# Infinity_Camera.net
KiCad netlist of a schematic drawn in EAGLE
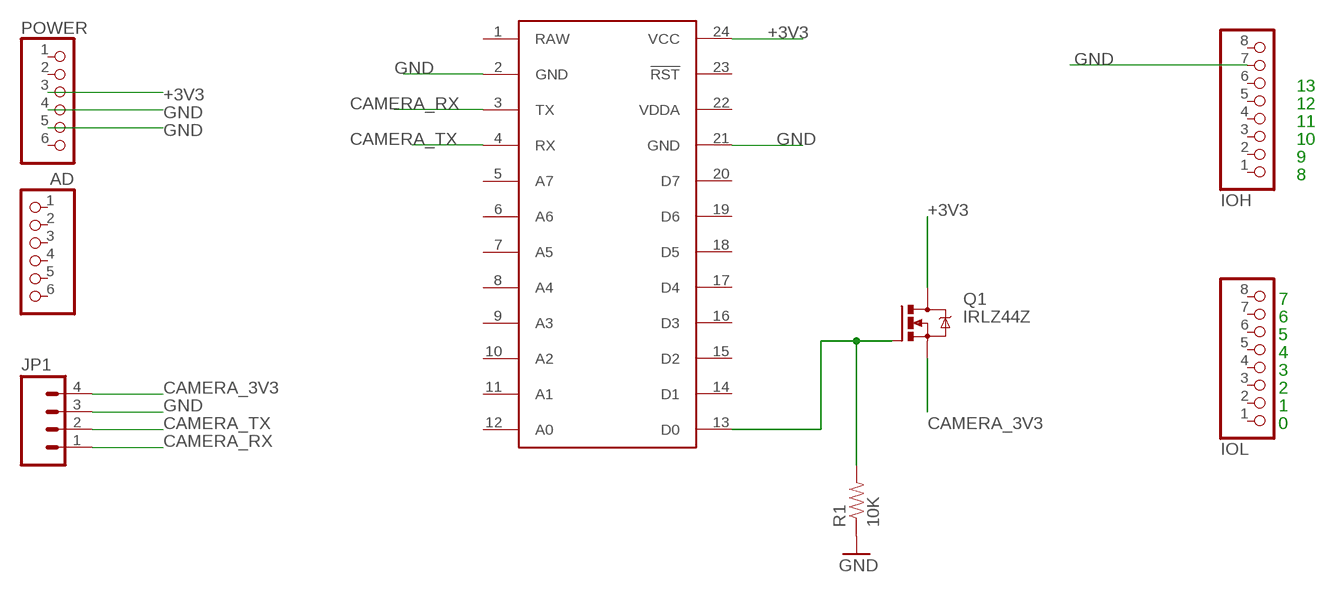
[diagram p0: schematic, sheet 1]

(export (version "E")
  (design (tool "Eeschema 10.0.6"))
  (components
    (comp (ref "AD")
      (value "PINHD-1X6")
      (footprint "eagle-import:1X06")
      (libsource (lib "eagle-import") (part "PINHD-1X6"))
    )
    (comp (ref "IOH")
      (value "PINHD-1X8")
      (footprint "eagle-import:1X08")
      (libsource (lib "eagle-import") (part "PINHD-1X8"))
    )
    (comp (ref "IOL")
      (value "PINHD-1X8")
      (footprint "eagle-import:1X08")
      (libsource (lib "eagle-import") (part "PINHD-1X8"))
    )
    (comp (ref "JP1")
      (value "M041.27MM")
      (footprint "eagle-import:1X04-1.27MM")
      (libsource (lib "eagle-import") (part "M041.27MM"))
    )
    (comp (ref "POWER")
      (value "PINHD-1X6")
      (footprint "eagle-import:1X06")
      (libsource (lib "eagle-import") (part "PINHD-1X6"))
    )
    (comp (ref "Q1")
      (value "IRLZ44Z")
      (footprint "eagle-import:TO220BH")
      (libsource (lib "eagle-import") (part "IRLZ44Z"))
    )
    (comp (ref "R1")
      (value "10K")
      (footprint "eagle-import:AXIAL-0.4")
      (libsource (lib "eagle-import") (part "RESISTORPTH-1/4W"))
    )
    (comp (ref "U$1")
      (value "SPARK_CORECORE")
      (footprint "eagle-import:SPARK_CORE")
      (libsource (lib "eagle-import") (part "SPARK_CORECORE"))
    )
  )
  (nets
    (net (code "1") (name "/+3V3") (class "Default")
      (node (ref "POWER") (pin "3") (pinfunction "3_3") (pintype "passive"))
      (node (ref "Q1") (pin "D") (pinfunction "D_D") (pintype "passive"))
      (node (ref "U$1") (pin "24") (pinfunction "VCC_24") (pintype "power_in"))
    )
    (net (code "2") (name "/CAMERA_3V3") (class "Default")
      (node (ref "JP1") (pin "4") (pinfunction "4_4") (pintype "passive"))
      (node (ref "Q1") (pin "S") (pinfunction "S_S") (pintype "passive"))
    )
    (net (code "3") (name "/CAMERA_RX") (class "Default")
      (node (ref "JP1") (pin "1") (pinfunction "1_1") (pintype "passive"))
      (node (ref "U$1") (pin "3") (pinfunction "TX_3") (pintype "bidirectional"))
    )
    (net (code "4") (name "/CAMERA_TX") (class "Default")
      (node (ref "JP1") (pin "2") (pinfunction "2_2") (pintype "passive"))
      (node (ref "U$1") (pin "4") (pinfunction "RX_4") (pintype "bidirectional"))
    )
    (net (code "5") (name "/RAW") (class "Default")
      (node (ref "U$1") (pin "1") (pinfunction "RAW_1") (pintype "power_in"))
    )
    (net (code "6") (name "/VDDA") (class "Default")
      (node (ref "U$1") (pin "22") (pinfunction "VDDA_22") (pintype "power_in"))
    )
    (net (code "7") (name "GND") (class "Default")
      (node (ref "IOH") (pin "7") (pinfunction "7_7") (pintype "passive"))
      (node (ref "JP1") (pin "3") (pinfunction "3_3") (pintype "passive"))
      (node (ref "POWER") (pin "4") (pinfunction "4_4") (pintype "passive"))
      (node (ref "POWER") (pin "5") (pinfunction "5_5") (pintype "passive"))
      (node (ref "R1") (pin "P$1") (pinfunction "1_P$1") (pintype "passive"))
      (node (ref "U$1") (pin "2") (pinfunction "GND_2") (pintype "power_in"))
      (node (ref "U$1") (pin "21") (pinfunction "GND_21") (pintype "power_in"))
    )
    (net (code "8") (name "Net-(R1-2)") (class "Default")
      (node (ref "Q1") (pin "G") (pinfunction "G_G") (pintype "passive"))
      (node (ref "R1") (pin "P$2") (pinfunction "2_P$2") (pintype "passive"))
      (node (ref "U$1") (pin "13") (pinfunction "D0_13") (pintype "bidirectional"))
    )
    (net (code "9") (name "unconnected-(AD-Pad1)") (class "Default")
      (node (ref "AD") (pin "1") (pinfunction "1_1") (pintype "passive"))
    )
    (net (code "10") (name "unconnected-(AD-Pad2)") (class "Default")
      (node (ref "AD") (pin "2") (pinfunction "2_2") (pintype "passive"))
    )
    (net (code "11") (name "unconnected-(AD-Pad3)") (class "Default")
      (node (ref "AD") (pin "3") (pinfunction "3_3") (pintype "passive"))
    )
    (net (code "12") (name "unconnected-(AD-Pad4)") (class "Default")
      (node (ref "AD") (pin "4") (pinfunction "4_4") (pintype "passive"))
    )
    (net (code "13") (name "unconnected-(AD-Pad5)") (class "Default")
      (node (ref "AD") (pin "5") (pinfunction "5_5") (pintype "passive"))
    )
    (net (code "14") (name "unconnected-(AD-Pad6)") (class "Default")
      (node (ref "AD") (pin "6") (pinfunction "6_6") (pintype "passive"))
    )
    (net (code "15") (name "unconnected-(IOH-Pad1)") (class "Default")
      (node (ref "IOH") (pin "1") (pinfunction "1_1") (pintype "passive"))
    )
    (net (code "16") (name "unconnected-(IOH-Pad2)") (class "Default")
      (node (ref "IOH") (pin "2") (pinfunction "2_2") (pintype "passive"))
    )
    (net (code "17") (name "unconnected-(IOH-Pad3)") (class "Default")
      (node (ref "IOH") (pin "3") (pinfunction "3_3") (pintype "passive"))
    )
    (net (code "18") (name "unconnected-(IOH-Pad4)") (class "Default")
      (node (ref "IOH") (pin "4") (pinfunction "4_4") (pintype "passive"))
    )
    (net (code "19") (name "unconnected-(IOH-Pad5)") (class "Default")
      (node (ref "IOH") (pin "5") (pinfunction "5_5") (pintype "passive"))
    )
    (net (code "20") (name "unconnected-(IOH-Pad6)") (class "Default")
      (node (ref "IOH") (pin "6") (pinfunction "6_6") (pintype "passive"))
    )
    (net (code "21") (name "unconnected-(IOH-Pad8)") (class "Default")
      (node (ref "IOH") (pin "8") (pinfunction "8_8") (pintype "passive"))
    )
    (net (code "22") (name "unconnected-(IOL-Pad1)") (class "Default")
      (node (ref "IOL") (pin "1") (pinfunction "1_1") (pintype "passive"))
    )
    (net (code "23") (name "unconnected-(IOL-Pad2)") (class "Default")
      (node (ref "IOL") (pin "2") (pinfunction "2_2") (pintype "passive"))
    )
    (net (code "24") (name "unconnected-(IOL-Pad3)") (class "Default")
      (node (ref "IOL") (pin "3") (pinfunction "3_3") (pintype "passive"))
    )
    (net (code "25") (name "unconnected-(IOL-Pad4)") (class "Default")
      (node (ref "IOL") (pin "4") (pinfunction "4_4") (pintype "passive"))
    )
    (net (code "26") (name "unconnected-(IOL-Pad5)") (class "Default")
      (node (ref "IOL") (pin "5") (pinfunction "5_5") (pintype "passive"))
    )
    (net (code "27") (name "unconnected-(IOL-Pad6)") (class "Default")
      (node (ref "IOL") (pin "6") (pinfunction "6_6") (pintype "passive"))
    )
    (net (code "28") (name "unconnected-(IOL-Pad7)") (class "Default")
      (node (ref "IOL") (pin "7") (pinfunction "7_7") (pintype "passive"))
    )
    (net (code "29") (name "unconnected-(IOL-Pad8)") (class "Default")
      (node (ref "IOL") (pin "8") (pinfunction "8_8") (pintype "passive"))
    )
    (net (code "30") (name "unconnected-(POWER-Pad1)") (class "Default")
      (node (ref "POWER") (pin "1") (pinfunction "1_1") (pintype "passive"))
    )
    (net (code "31") (name "unconnected-(POWER-Pad2)") (class "Default")
      (node (ref "POWER") (pin "2") (pinfunction "2_2") (pintype "passive"))
    )
    (net (code "32") (name "unconnected-(POWER-Pad6)") (class "Default")
      (node (ref "POWER") (pin "6") (pinfunction "6_6") (pintype "passive"))
    )
    (net (code "33") (name "unconnected-(U$1-A0-Pad12)") (class "Default")
      (node (ref "U$1") (pin "12") (pinfunction "A0_12") (pintype "bidirectional"))
    )
    (net (code "34") (name "unconnected-(U$1-A1-Pad11)") (class "Default")
      (node (ref "U$1") (pin "11") (pinfunction "A1_11") (pintype "bidirectional"))
    )
    (net (code "35") (name "unconnected-(U$1-A2-Pad10)") (class "Default")
      (node (ref "U$1") (pin "10") (pinfunction "A2_10") (pintype "bidirectional"))
    )
    (net (code "36") (name "unconnected-(U$1-A3-Pad9)") (class "Default")
      (node (ref "U$1") (pin "9") (pinfunction "A3_9") (pintype "bidirectional"))
    )
    (net (code "37") (name "unconnected-(U$1-A4-Pad8)") (class "Default")
      (node (ref "U$1") (pin "8") (pinfunction "A4_8") (pintype "bidirectional"))
    )
    (net (code "38") (name "unconnected-(U$1-A5-Pad7)") (class "Default")
      (node (ref "U$1") (pin "7") (pinfunction "A5_7") (pintype "bidirectional"))
    )
    (net (code "39") (name "unconnected-(U$1-A6-Pad6)") (class "Default")
      (node (ref "U$1") (pin "6") (pinfunction "A6_6") (pintype "bidirectional"))
    )
    (net (code "40") (name "unconnected-(U$1-A7-Pad5)") (class "Default")
      (node (ref "U$1") (pin "5") (pinfunction "A7_5") (pintype "bidirectional"))
    )
    (net (code "41") (name "unconnected-(U$1-D1-Pad14)") (class "Default")
      (node (ref "U$1") (pin "14") (pinfunction "D1_14") (pintype "bidirectional"))
    )
    (net (code "42") (name "unconnected-(U$1-D2-Pad15)") (class "Default")
      (node (ref "U$1") (pin "15") (pinfunction "D2_15") (pintype "bidirectional"))
    )
    (net (code "43") (name "unconnected-(U$1-D3-Pad16)") (class "Default")
      (node (ref "U$1") (pin "16") (pinfunction "D3_16") (pintype "bidirectional"))
    )
    (net (code "44") (name "unconnected-(U$1-D4-Pad17)") (class "Default")
      (node (ref "U$1") (pin "17") (pinfunction "D4_17") (pintype "bidirectional"))
    )
    (net (code "45") (name "unconnected-(U$1-D5-Pad18)") (class "Default")
      (node (ref "U$1") (pin "18") (pinfunction "D5_18") (pintype "bidirectional"))
    )
    (net (code "46") (name "unconnected-(U$1-D6-Pad19)") (class "Default")
      (node (ref "U$1") (pin "19") (pinfunction "D6_19") (pintype "bidirectional"))
    )
    (net (code "47") (name "unconnected-(U$1-D7-Pad20)") (class "Default")
      (node (ref "U$1") (pin "20") (pinfunction "D7_20") (pintype "bidirectional"))
    )
    (net (code "48") (name "unconnected-(U$1-~{RST}-Pad23)") (class "Default")
      (node (ref "U$1") (pin "23") (pinfunction "~{RST}_23") (pintype "bidirectional"))
    )
  )
)
